# ASM2021.net
KiCad netlist of a schematic drawn in EAGLE
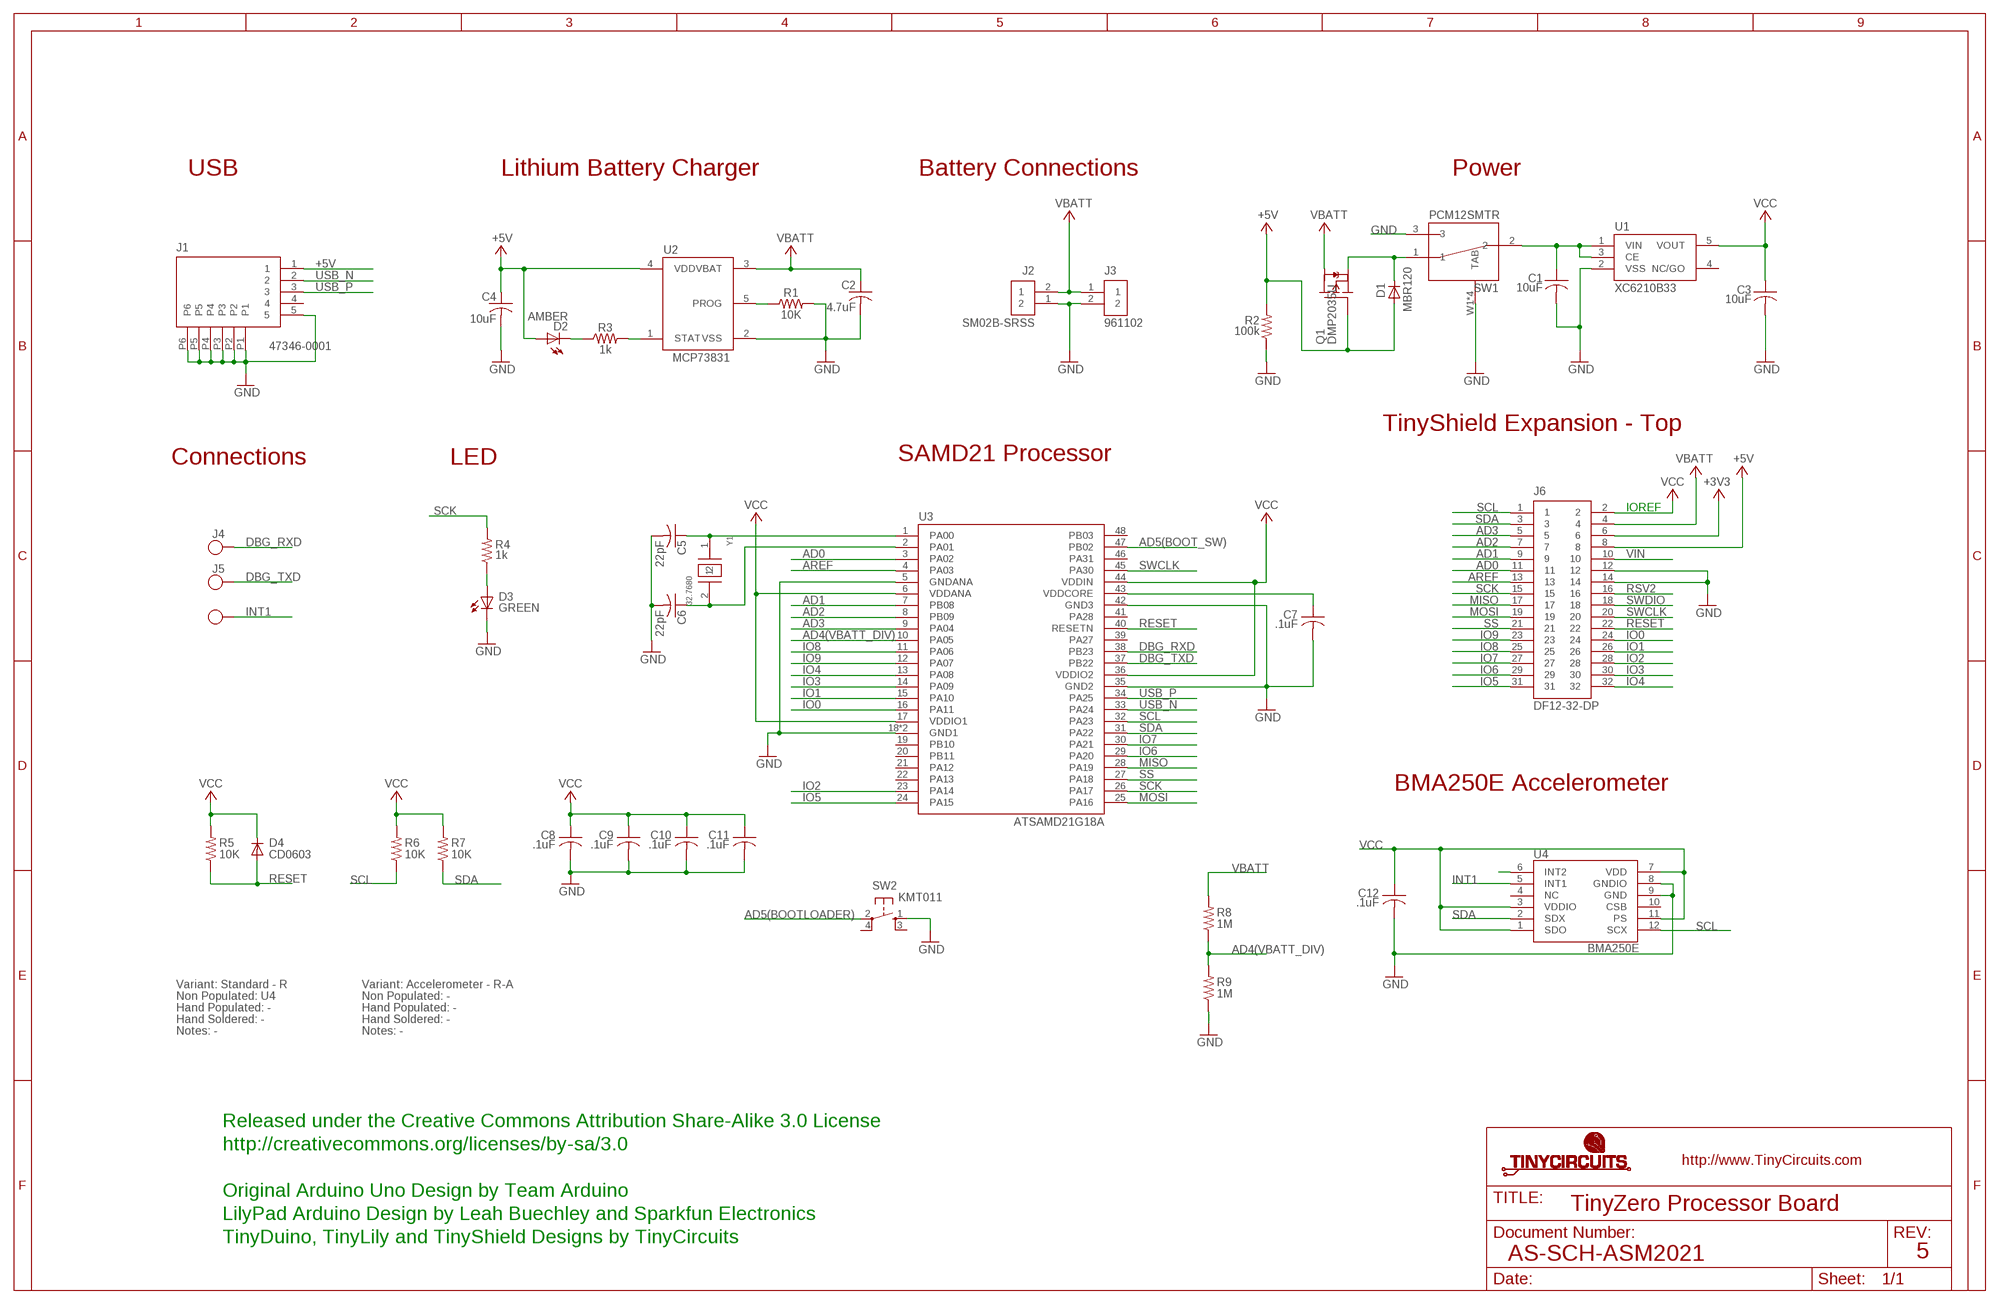
[diagram p0: schematic, sheet 1]

(export (version "E")
  (design (tool "Eeschema 10.0.6"))
  (components
    (comp (ref "C1")
      (value "10uF")
      (footprint "eagle-import:C0603")
      (fields (field (name "PARTNO") "AS-ITM-00002") (field (name "PARTNO_1") "AS-ITM-00002"))
      (libsource (lib "eagle-import") (part "AS-ITM-00002"))
    )
    (comp (ref "C2")
      (value "4.7uF")
      (footprint "eagle-import:C0603")
      (fields (field (name "PARTNO") "AS-ITM-00088") (field (name "PARTNO_1") "AS-ITM-00088"))
      (libsource (lib "eagle-import") (part "AS-ITM-00088"))
    )
    (comp (ref "C3")
      (value "10uF")
      (footprint "eagle-import:C0603")
      (fields (field (name "PARTNO") "AS-ITM-00002") (field (name "PARTNO_1") "AS-ITM-00002"))
      (libsource (lib "eagle-import") (part "AS-ITM-00002"))
    )
    (comp (ref "C4")
      (value "10uF")
      (footprint "eagle-import:C0603")
      (fields (field (name "PARTNO") "AS-ITM-00002") (field (name "PARTNO_1") "AS-ITM-00002"))
      (libsource (lib "eagle-import") (part "AS-ITM-00002"))
    )
    (comp (ref "C5")
      (value "22pF")
      (footprint "eagle-import:C0402")
      (fields (field (name "PARTNO") "AS-ITM-00211") (field (name "PARTNO_1") "AS-ITM-00211"))
      (libsource (lib "eagle-import") (part "AS-ITM-00211"))
    )
    (comp (ref "C6")
      (value "22pF")
      (footprint "eagle-import:C0402")
      (fields (field (name "PARTNO") "AS-ITM-00211") (field (name "PARTNO_1") "AS-ITM-00211"))
      (libsource (lib "eagle-import") (part "AS-ITM-00211"))
    )
    (comp (ref "C7")
      (value ".1uF")
      (footprint "eagle-import:C0402")
      (fields (field (name "PARTNO") "AS-ITM-00008") (field (name "PARTNO_1") "AS-ITM-00008"))
      (libsource (lib "eagle-import") (part "AS-ITM-00008"))
    )
    (comp (ref "C8")
      (value ".1uF")
      (footprint "eagle-import:C0402")
      (fields (field (name "PARTNO") "AS-ITM-00008") (field (name "PARTNO_1") "AS-ITM-00008"))
      (libsource (lib "eagle-import") (part "AS-ITM-00008"))
    )
    (comp (ref "C9")
      (value ".1uF")
      (footprint "eagle-import:C0402")
      (fields (field (name "PARTNO") "AS-ITM-00008") (field (name "PARTNO_1") "AS-ITM-00008"))
      (libsource (lib "eagle-import") (part "AS-ITM-00008"))
    )
    (comp (ref "C10")
      (value ".1uF")
      (footprint "eagle-import:C0402")
      (fields (field (name "PARTNO") "AS-ITM-00008") (field (name "PARTNO_1") "AS-ITM-00008"))
      (libsource (lib "eagle-import") (part "AS-ITM-00008"))
    )
    (comp (ref "C11")
      (value ".1uF")
      (footprint "eagle-import:C0402")
      (fields (field (name "PARTNO") "AS-ITM-00008") (field (name "PARTNO_1") "AS-ITM-00008"))
      (libsource (lib "eagle-import") (part "AS-ITM-00008"))
    )
    (comp (ref "C12")
      (value ".1uF")
      (footprint "eagle-import:C0402")
      (fields (field (name "PARTNO") "AS-ITM-00008") (field (name "PARTNO_1") "AS-ITM-00008"))
      (libsource (lib "eagle-import") (part "AS-ITM-00008"))
    )
    (comp (ref "D1")
      (value "MBR120")
      (footprint "eagle-import:SOD-123FL")
      (fields (field (name "PARTNO") "AS-ITM-00111"))
      (libsource (lib "eagle-import") (part "AS-ITM-00111"))
    )
    (comp (ref "D2")
      (value "AMBER")
      (footprint "eagle-import:LNJ_LED")
      (fields (field (name "PARTNO") "AS-ITM-00026") (field (name "PARTNO_1") "AS-ITM-00026"))
      (libsource (lib "eagle-import") (part "AS-ITM-00026"))
    )
    (comp (ref "D3")
      (value "GREEN")
      (footprint "eagle-import:LNJ_LED")
      (fields (field (name "PARTNO") "AS-ITM-00011") (field (name "PARTNO_1") "AS-ITM-00011"))
      (libsource (lib "eagle-import") (part "AS-ITM-00011"))
    )
    (comp (ref "D4")
      (value "CD0603")
      (footprint "eagle-import:0603")
      (fields (field (name "PARTNO") "AS-ITM-00009") (field (name "PARTNO_1") "AS-ITM-00009"))
      (libsource (lib "eagle-import") (part "AS-ITM-00009"))
    )
    (comp (ref "J1")
      (value "47346-0001")
      (footprint "eagle-import:MICRO_USB")
      (fields (field (name "PARTNO") "AS-ITM-00021"))
      (libsource (lib "eagle-import") (part "AS-ITM-00021"))
    )
    (comp (ref "J2")
      (value "SM02B-SRSS")
      (footprint "eagle-import:JST_SH_2X1")
      (fields (field (name "PARTNO") "AS-ITM-00231"))
      (libsource (lib "eagle-import") (part "AS-ITM-00231"))
    )
    (comp (ref "J3")
      (value "961102")
      (footprint "eagle-import:2X.1_")
      (fields (field (name "PARTNO") "AS-ITM-00044"))
      (libsource (lib "eagle-import") (part "AS-ITM-00044"))
    )
    (comp (ref "J4")
      (value "TEST_POINT")
      (footprint "eagle-import:TEST_POINT_1MM")
      (libsource (lib "eagle-import") (part "TEST_POINT"))
    )
    (comp (ref "J5")
      (value "TEST_POINT")
      (footprint "eagle-import:TEST_POINT_1MM")
      (libsource (lib "eagle-import") (part "TEST_POINT"))
    )
    (comp (ref "J6")
      (value "DF12-32-DP")
      (footprint "eagle-import:DF12-32-DP")
      (fields (field (name "PARTNO") "AS-ITM-00015") (field (name "PARTNO_1") "AS-ITM-00015"))
      (libsource (lib "eagle-import") (part "AS-ITM-00015"))
    )
    (comp (ref "Q1")
      (value "DMP2035U")
      (footprint "eagle-import:SOT23")
      (fields (field (name "PARTNO") "AS-ITM-00024"))
      (libsource (lib "eagle-import") (part "AS-ITM-00024"))
    )
    (comp (ref "R1")
      (value "10K")
      (footprint "eagle-import:0402")
      (fields (field (name "PARTNO") "AS-ITM-00032"))
      (libsource (lib "eagle-import") (part "AS-ITM-00032"))
    )
    (comp (ref "R2")
      (value "100k")
      (footprint "eagle-import:0402")
      (fields (field (name "PARTNO") "AS-ITM-00004") (field (name "PARTNO_1") "AS-ITM-00004"))
      (libsource (lib "eagle-import") (part "AS-ITM-00004"))
    )
    (comp (ref "R3")
      (value "1k")
      (footprint "eagle-import:0402")
      (fields (field (name "PARTNO") "AS-ITM-00003") (field (name "PARTNO_1") "AS-ITM-00003"))
      (libsource (lib "eagle-import") (part "AS-ITM-00003"))
    )
    (comp (ref "R4")
      (value "1k")
      (footprint "eagle-import:0402")
      (fields (field (name "PARTNO") "AS-ITM-00003") (field (name "PARTNO_1") "AS-ITM-00003"))
      (libsource (lib "eagle-import") (part "AS-ITM-00003"))
    )
    (comp (ref "R5")
      (value "10K")
      (footprint "eagle-import:0402")
      (fields (field (name "PARTNO") "AS-ITM-00032") (field (name "PARTNO_1") "AS-ITM-00032"))
      (libsource (lib "eagle-import") (part "AS-ITM-00032"))
    )
    (comp (ref "R6")
      (value "10K")
      (footprint "eagle-import:0402")
      (fields (field (name "PARTNO") "AS-ITM-00032") (field (name "PARTNO_1") "AS-ITM-00032"))
      (libsource (lib "eagle-import") (part "AS-ITM-00032"))
    )
    (comp (ref "R7")
      (value "10K")
      (footprint "eagle-import:0402")
      (fields (field (name "PARTNO") "AS-ITM-00032") (field (name "PARTNO_1") "AS-ITM-00032"))
      (libsource (lib "eagle-import") (part "AS-ITM-00032"))
    )
    (comp (ref "R8")
      (value "1M")
      (footprint "eagle-import:0402")
      (fields (field (name "PARTNO") "AS-ITM-00005") (field (name "PARTNO_1") "AS-ITM-00005"))
      (libsource (lib "eagle-import") (part "AS-ITM-00005"))
    )
    (comp (ref "R9")
      (value "1M")
      (footprint "eagle-import:0402")
      (fields (field (name "PARTNO") "AS-ITM-00005") (field (name "PARTNO_1") "AS-ITM-00005"))
      (libsource (lib "eagle-import") (part "AS-ITM-00005"))
    )
    (comp (ref "SW1")
      (value "PCM12SMTR")
      (footprint "eagle-import:PCM12SMTR")
      (fields (field (name "PARTNO") "AS-ITM-00220"))
      (libsource (lib "eagle-import") (part "AS-ITM-00220"))
    )
    (comp (ref "SW2")
      (value "KMT011")
      (footprint "eagle-import:KMT011")
      (fields (field (name "PARTNO") "AS-ITM-00041"))
      (libsource (lib "eagle-import") (part "AS-ITM-00041"))
    )
    (comp (ref "U1")
      (value "XC6210B33")
      (footprint "eagle-import:SOT-25")
      (fields (field (name "PARTNO") "AS-ITM-00046"))
      (libsource (lib "eagle-import") (part "AS-ITM-00046"))
    )
    (comp (ref "U2")
      (value "MCP73831")
      (footprint "eagle-import:SOT-23")
      (fields (field (name "PARTNO") "AS-ITM-00136"))
      (libsource (lib "eagle-import") (part "AS-ITM-00136"))
    )
    (comp (ref "U3")
      (value "ATSAMD21G18A")
      (footprint "eagle-import:QFN48")
      (fields (field (name "PARTNO") "AS-ITM-00273") (field (name "PARTNO_1") "AS-ITM-00273"))
      (libsource (lib "eagle-import") (part "AS-ITM-00273"))
    )
    (comp (ref "U4")
      (value "BMA250E")
      (footprint "eagle-import:3-AXIS_ACCELEROMETER")
      (fields (field (name "PARTNO") "AS-ITM-00070"))
      (libsource (lib "eagle-import") (part "AS-ITM-00070"))
    )
    (comp (ref "Y1")
      (value "32.7680")
      (footprint "eagle-import:ABS06")
      (fields (field (name "PARTNO") "AS-ITM-00279") (field (name "PARTNO_1") "AS-ITM-00279"))
      (libsource (lib "eagle-import") (part "AS-ITM-00279"))
    )
  )
  (nets
    (net (code "1") (name "+3V3") (class "Default")
      (node (ref "J6") (pin "6") (pinfunction "6_6") (pintype "bidirectional"))
    )
    (net (code "2") (name "+5V") (class "Default")
      (node (ref "C4") (pin "1") (pinfunction "1_1") (pintype "passive"))
      (node (ref "D1") (pin "A") (pinfunction "A_A") (pintype "passive"))
      (node (ref "D2") (pin "A") (pinfunction "A_A") (pintype "passive"))
      (node (ref "J1") (pin "1") (pinfunction "1_1") (pintype "bidirectional"))
      (node (ref "J6") (pin "8") (pinfunction "8_8") (pintype "bidirectional"))
      (node (ref "Q1") (pin "B") (pinfunction "G_B") (pintype "passive"))
      (node (ref "R2") (pin "2") (pinfunction "2_2") (pintype "passive"))
      (node (ref "U2") (pin "4") (pinfunction "VDD_4") (pintype "bidirectional"))
    )
    (net (code "3") (name "/AD0") (class "Default")
      (node (ref "J6") (pin "11") (pinfunction "11_11") (pintype "bidirectional"))
      (node (ref "U3") (pin "3") (pinfunction "PA02_3") (pintype "bidirectional"))
    )
    (net (code "4") (name "/AD1") (class "Default")
      (node (ref "J6") (pin "9") (pinfunction "9_9") (pintype "bidirectional"))
      (node (ref "U3") (pin "7") (pinfunction "PB08_7") (pintype "bidirectional"))
    )
    (net (code "5") (name "/AD2") (class "Default")
      (node (ref "J6") (pin "7") (pinfunction "7_7") (pintype "bidirectional"))
      (node (ref "U3") (pin "8") (pinfunction "PB09_8") (pintype "bidirectional"))
    )
    (net (code "6") (name "/AD3") (class "Default")
      (node (ref "J6") (pin "5") (pinfunction "5_5") (pintype "bidirectional"))
      (node (ref "U3") (pin "9") (pinfunction "PA04_9") (pintype "bidirectional"))
    )
    (net (code "7") (name "/AD4(VBATT_DIV)") (class "Default")
      (node (ref "R8") (pin "1") (pinfunction "1_1") (pintype "passive"))
      (node (ref "R9") (pin "2") (pinfunction "2_2") (pintype "passive"))
      (node (ref "U3") (pin "10") (pinfunction "PA05_10") (pintype "bidirectional"))
    )
    (net (code "8") (name "/AD5(BOOTLOADER)") (class "Default")
      (node (ref "SW2") (pin "2") (pinfunction "2_2") (pintype "passive"))
    )
    (net (code "9") (name "/AD5(BOOT_SW)") (class "Default")
      (node (ref "U3") (pin "47") (pinfunction "PB02_47") (pintype "bidirectional"))
    )
    (net (code "10") (name "/AREF") (class "Default")
      (node (ref "J6") (pin "13") (pinfunction "13_13") (pintype "bidirectional"))
      (node (ref "U3") (pin "4") (pinfunction "PA03_4") (pintype "bidirectional"))
    )
    (net (code "11") (name "/DBG_RXD") (class "Default")
      (node (ref "J4") (pin "P$1") (pinfunction "1_P$1") (pintype "bidirectional"))
      (node (ref "U3") (pin "38") (pinfunction "PB23_38") (pintype "bidirectional"))
    )
    (net (code "12") (name "/DBG_TXD") (class "Default")
      (node (ref "J5") (pin "P$1") (pinfunction "1_P$1") (pintype "bidirectional"))
      (node (ref "U3") (pin "37") (pinfunction "PB22_37") (pintype "bidirectional"))
    )
    (net (code "13") (name "/INT1") (class "Default")
      (node (ref "U4") (pin "5") (pinfunction "INT1_5") (pintype "bidirectional"))
    )
    (net (code "14") (name "/IO0") (class "Default")
      (node (ref "J6") (pin "24") (pinfunction "24_24") (pintype "bidirectional"))
      (node (ref "U3") (pin "16") (pinfunction "PA11_16") (pintype "bidirectional"))
    )
    (net (code "15") (name "/IO1") (class "Default")
      (node (ref "J6") (pin "26") (pinfunction "26_26") (pintype "bidirectional"))
      (node (ref "U3") (pin "15") (pinfunction "PA10_15") (pintype "bidirectional"))
    )
    (net (code "16") (name "/IO2") (class "Default")
      (node (ref "J6") (pin "28") (pinfunction "28_28") (pintype "bidirectional"))
      (node (ref "U3") (pin "23") (pinfunction "PA14_23") (pintype "bidirectional"))
    )
    (net (code "17") (name "/IO3") (class "Default")
      (node (ref "J6") (pin "30") (pinfunction "30_30") (pintype "bidirectional"))
      (node (ref "U3") (pin "14") (pinfunction "PA09_14") (pintype "bidirectional"))
    )
    (net (code "18") (name "/IO4") (class "Default")
      (node (ref "J6") (pin "32") (pinfunction "32_32") (pintype "bidirectional"))
      (node (ref "U3") (pin "13") (pinfunction "PA08_13") (pintype "bidirectional"))
    )
    (net (code "19") (name "/IO5") (class "Default")
      (node (ref "J6") (pin "31") (pinfunction "31_31") (pintype "bidirectional"))
      (node (ref "U3") (pin "24") (pinfunction "PA15_24") (pintype "bidirectional"))
    )
    (net (code "20") (name "/IO6") (class "Default")
      (node (ref "J6") (pin "29") (pinfunction "29_29") (pintype "bidirectional"))
      (node (ref "U3") (pin "29") (pinfunction "PA20_29") (pintype "bidirectional"))
    )
    (net (code "21") (name "/IO7") (class "Default")
      (node (ref "J6") (pin "27") (pinfunction "27_27") (pintype "bidirectional"))
      (node (ref "U3") (pin "30") (pinfunction "PA21_30") (pintype "bidirectional"))
    )
    (net (code "22") (name "/IO8") (class "Default")
      (node (ref "J6") (pin "25") (pinfunction "25_25") (pintype "bidirectional"))
      (node (ref "U3") (pin "11") (pinfunction "PA06_11") (pintype "bidirectional"))
    )
    (net (code "23") (name "/IO9") (class "Default")
      (node (ref "J6") (pin "23") (pinfunction "23_23") (pintype "bidirectional"))
      (node (ref "U3") (pin "12") (pinfunction "PA07_12") (pintype "bidirectional"))
    )
    (net (code "24") (name "/MISO") (class "Default")
      (node (ref "J6") (pin "17") (pinfunction "17_17") (pintype "bidirectional"))
      (node (ref "U3") (pin "28") (pinfunction "PA19_28") (pintype "bidirectional"))
    )
    (net (code "25") (name "/MOSI") (class "Default")
      (node (ref "J6") (pin "19") (pinfunction "19_19") (pintype "bidirectional"))
      (node (ref "U3") (pin "25") (pinfunction "PA16_25") (pintype "bidirectional"))
    )
    (net (code "26") (name "/RESET") (class "Default")
      (node (ref "D4") (pin "A") (pinfunction "A_A") (pintype "passive"))
      (node (ref "J6") (pin "22") (pinfunction "22_22") (pintype "bidirectional"))
      (node (ref "R5") (pin "1") (pinfunction "1_1") (pintype "passive"))
      (node (ref "U3") (pin "40") (pinfunction "RESETN_40") (pintype "bidirectional"))
    )
    (net (code "27") (name "/RSV2") (class "Default")
      (node (ref "J6") (pin "16") (pinfunction "16_16") (pintype "bidirectional"))
    )
    (net (code "28") (name "/SCK") (class "Default")
      (node (ref "J6") (pin "15") (pinfunction "15_15") (pintype "bidirectional"))
      (node (ref "R4") (pin "2") (pinfunction "2_2") (pintype "passive"))
      (node (ref "U3") (pin "26") (pinfunction "PA17_26") (pintype "bidirectional"))
    )
    (net (code "29") (name "/SCL") (class "Default")
      (node (ref "J6") (pin "1") (pinfunction "1_1") (pintype "bidirectional"))
      (node (ref "R6") (pin "1") (pinfunction "1_1") (pintype "passive"))
      (node (ref "U3") (pin "32") (pinfunction "PA23_32") (pintype "bidirectional"))
      (node (ref "U4") (pin "12") (pinfunction "SCX_12") (pintype "bidirectional"))
    )
    (net (code "30") (name "/SDA") (class "Default")
      (node (ref "J6") (pin "3") (pinfunction "3_3") (pintype "bidirectional"))
      (node (ref "R7") (pin "1") (pinfunction "1_1") (pintype "passive"))
      (node (ref "U3") (pin "31") (pinfunction "PA22_31") (pintype "bidirectional"))
      (node (ref "U4") (pin "2") (pinfunction "SDX_2") (pintype "bidirectional"))
    )
    (net (code "31") (name "/SS") (class "Default")
      (node (ref "J6") (pin "21") (pinfunction "21_21") (pintype "bidirectional"))
      (node (ref "U3") (pin "27") (pinfunction "PA18_27") (pintype "bidirectional"))
    )
    (net (code "32") (name "/SWCLK") (class "Default")
      (node (ref "J6") (pin "20") (pinfunction "20_20") (pintype "bidirectional"))
      (node (ref "U3") (pin "45") (pinfunction "PA30_45") (pintype "bidirectional"))
    )
    (net (code "33") (name "/SWDIO") (class "Default")
      (node (ref "J6") (pin "18") (pinfunction "18_18") (pintype "bidirectional"))
    )
    (net (code "34") (name "/USB_N") (class "Default")
      (node (ref "J1") (pin "2") (pinfunction "2_2") (pintype "bidirectional"))
      (node (ref "U3") (pin "33") (pinfunction "PA24_33") (pintype "bidirectional"))
    )
    (net (code "35") (name "/USB_P") (class "Default")
      (node (ref "J1") (pin "3") (pinfunction "3_3") (pintype "bidirectional"))
      (node (ref "U3") (pin "34") (pinfunction "PA25_34") (pintype "bidirectional"))
    )
    (net (code "36") (name "/VIN") (class "Default")
      (node (ref "J6") (pin "10") (pinfunction "10_10") (pintype "bidirectional"))
    )
    (net (code "37") (name "GND") (class "Default")
      (node (ref "C1") (pin "2") (pinfunction "2_2") (pintype "passive"))
      (node (ref "C10") (pin "2") (pinfunction "2_2") (pintype "passive"))
      (node (ref "C11") (pin "2") (pinfunction "2_2") (pintype "passive"))
      (node (ref "C12") (pin "2") (pinfunction "2_2") (pintype "passive"))
      (node (ref "C2") (pin "2") (pinfunction "2_2") (pintype "passive"))
      (node (ref "C3") (pin "2") (pinfunction "2_2") (pintype "passive"))
      (node (ref "C4") (pin "2") (pinfunction "2_2") (pintype "passive"))
      (node (ref "C5") (pin "2") (pinfunction "2_2") (pintype "passive"))
      (node (ref "C6") (pin "2") (pinfunction "2_2") (pintype "passive"))
      (node (ref "C7") (pin "2") (pinfunction "2_2") (pintype "passive"))
      (node (ref "C8") (pin "2") (pinfunction "2_2") (pintype "passive"))
      (node (ref "C9") (pin "2") (pinfunction "2_2") (pintype "passive"))
      (node (ref "D3") (pin "C") (pinfunction "C_C") (pintype "passive"))
      (node (ref "J1") (pin "5") (pinfunction "5_5") (pintype "bidirectional"))
      (node (ref "J1") (pin "P1") (pinfunction "P1_P1") (pintype "bidirectional"))
      (node (ref "J1") (pin "P2") (pinfunction "P2_P2") (pintype "bidirectional"))
      (node (ref "J1") (pin "P3") (pinfunction "P3_P3") (pintype "bidirectional"))
      (node (ref "J1") (pin "P4") (pinfunction "P4_P4") (pintype "bidirectional"))
      (node (ref "J1") (pin "P5") (pinfunction "P5_P5") (pintype "bidirectional"))
      (node (ref "J1") (pin "P6") (pinfunction "P6_P6") (pintype "bidirectional"))
      (node (ref "J2") (pin "1") (pinfunction "2_1") (pintype "bidirectional"))
      (node (ref "J3") (pin "2") (pinfunction "2_2") (pintype "bidirectional"))
      (node (ref "J6") (pin "12") (pinfunction "12_12") (pintype "bidirectional"))
      (node (ref "J6") (pin "14") (pinfunction "14_14") (pintype "bidirectional"))
      (node (ref "R1") (pin "2") (pinfunction "2_2") (pintype "passive"))
      (node (ref "R2") (pin "1") (pinfunction "1_1") (pintype "passive"))
      (node (ref "R9") (pin "1") (pinfunction "1_1") (pintype "passive"))
      (node (ref "SW1") (pin "3") (pinfunction "3_3") (pintype "bidirectional"))
      (node (ref "SW1") (pin "W1") (pinfunction "TAB_W1") (pintype "bidirectional"))
      (node (ref "SW1") (pin "W2") (pinfunction "TAB_W2") (pintype "bidirectional"))
      (node (ref "SW1") (pin "W3") (pinfunction "TAB_W3") (pintype "bidirectional"))
      (node (ref "SW1") (pin "W4") (pinfunction "TAB_W4") (pintype "bidirectional"))
      (node (ref "SW2") (pin "1") (pinfunction "1_1") (pintype "passive"))
      (node (ref "U1") (pin "2") (pinfunction "VSS_2") (pintype "power_in"))
      (node (ref "U2") (pin "2") (pinfunction "VSS_2") (pintype "bidirectional"))
      (node (ref "U3") (pin "18") (pinfunction "GND1_18") (pintype "bidirectional"))
      (node (ref "U3") (pin "35") (pinfunction "GND2_35") (pintype "bidirectional"))
      (node (ref "U3") (pin "42") (pinfunction "GND3_42") (pintype "bidirectional"))
      (node (ref "U3") (pin "5") (pinfunction "GNDANA_5") (pintype "bidirectional"))
      (node (ref "U3") (pin "EXP") (pinfunction "GND1_EXP") (pintype "bidirectional"))
      (node (ref "U4") (pin "8") (pinfunction "GNDIO_8") (pintype "bidirectional"))
      (node (ref "U4") (pin "9") (pinfunction "GND_9") (pintype "bidirectional"))
    )
    (net (code "38") (name "Net-(D2-PadC)") (class "Default")
      (node (ref "D2") (pin "C") (pinfunction "C_C") (pintype "passive"))
      (node (ref "R3") (pin "1") (pinfunction "1_1") (pintype "passive"))
    )
    (net (code "39") (name "Net-(D3-PadA)") (class "Default")
      (node (ref "D3") (pin "A") (pinfunction "A_A") (pintype "passive"))
      (node (ref "R4") (pin "1") (pinfunction "1_1") (pintype "passive"))
    )
    (net (code "40") (name "Net-(Q1-S)") (class "Default")
      (node (ref "D1") (pin "C") (pinfunction "C_C") (pintype "passive"))
      (node (ref "Q1") (pin "E") (pinfunction "S_E") (pintype "passive"))
      (node (ref "SW1") (pin "1") (pinfunction "1_1") (pintype "bidirectional"))
    )
    (net (code "41") (name "Net-(U1-CE)") (class "Default")
      (node (ref "C1") (pin "1") (pinfunction "1_1") (pintype "passive"))
      (node (ref "SW1") (pin "2") (pinfunction "2_2") (pintype "bidirectional"))
      (node (ref "U1") (pin "1") (pinfunction "VIN_1") (pintype "bidirectional"))
      (node (ref "U1") (pin "3") (pinfunction "CE_3") (pintype "bidirectional"))
    )
    (net (code "42") (name "Net-(U2-PROG)") (class "Default")
      (node (ref "R1") (pin "1") (pinfunction "1_1") (pintype "passive"))
      (node (ref "U2") (pin "5") (pinfunction "PROG_5") (pintype "bidirectional"))
    )
    (net (code "43") (name "Net-(U2-STAT)") (class "Default")
      (node (ref "R3") (pin "2") (pinfunction "2_2") (pintype "passive"))
      (node (ref "U2") (pin "1") (pinfunction "STAT_1") (pintype "bidirectional"))
    )
    (net (code "44") (name "Net-(U3-PA00)") (class "Default")
      (node (ref "C5") (pin "1") (pinfunction "1_1") (pintype "passive"))
      (node (ref "U3") (pin "1") (pinfunction "PA00_1") (pintype "bidirectional"))
      (node (ref "Y1") (pin "1") (pinfunction "1_1") (pintype "bidirectional"))
    )
    (net (code "45") (name "Net-(U3-PA01)") (class "Default")
      (node (ref "C6") (pin "1") (pinfunction "1_1") (pintype "passive"))
      (node (ref "U3") (pin "2") (pinfunction "PA01_2") (pintype "bidirectional"))
      (node (ref "Y1") (pin "2") (pinfunction "2_2") (pintype "bidirectional"))
    )
    (net (code "46") (name "Net-(U3-VDDCORE)") (class "Default")
      (node (ref "C7") (pin "1") (pinfunction "1_1") (pintype "passive"))
      (node (ref "U3") (pin "43") (pinfunction "VDDCORE_43") (pintype "bidirectional"))
    )
    (net (code "47") (name "VBATT") (class "Default")
      (node (ref "C2") (pin "1") (pinfunction "1_1") (pintype "passive"))
      (node (ref "J2") (pin "2") (pinfunction "1_2") (pintype "bidirectional"))
      (node (ref "J3") (pin "1") (pinfunction "1_1") (pintype "bidirectional"))
      (node (ref "J6") (pin "4") (pinfunction "4_4") (pintype "bidirectional"))
      (node (ref "Q1") (pin "C") (pinfunction "D_C") (pintype "passive"))
      (node (ref "R8") (pin "2") (pinfunction "2_2") (pintype "passive"))
      (node (ref "U2") (pin "3") (pinfunction "VBAT_3") (pintype "bidirectional"))
    )
    (net (code "48") (name "VCC") (class "Default")
      (node (ref "C10") (pin "1") (pinfunction "1_1") (pintype "passive"))
      (node (ref "C11") (pin "1") (pinfunction "1_1") (pintype "passive"))
      (node (ref "C12") (pin "1") (pinfunction "1_1") (pintype "passive"))
      (node (ref "C3") (pin "1") (pinfunction "1_1") (pintype "passive"))
      (node (ref "C8") (pin "1") (pinfunction "1_1") (pintype "passive"))
      (node (ref "C9") (pin "1") (pinfunction "1_1") (pintype "passive"))
      (node (ref "D4") (pin "C") (pinfunction "C_C") (pintype "passive"))
      (node (ref "J6") (pin "2") (pinfunction "2_2") (pintype "bidirectional"))
      (node (ref "R5") (pin "2") (pinfunction "2_2") (pintype "passive"))
      (node (ref "R6") (pin "2") (pinfunction "2_2") (pintype "passive"))
      (node (ref "R7") (pin "2") (pinfunction "2_2") (pintype "passive"))
      (node (ref "U1") (pin "5") (pinfunction "VOUT_5") (pintype "bidirectional"))
      (node (ref "U3") (pin "17") (pinfunction "VDDIO1_17") (pintype "bidirectional"))
      (node (ref "U3") (pin "36") (pinfunction "VDDIO2_36") (pintype "bidirectional"))
      (node (ref "U3") (pin "44") (pinfunction "VDDIN_44") (pintype "bidirectional"))
      (node (ref "U3") (pin "6") (pinfunction "VDDANA_6") (pintype "bidirectional"))
      (node (ref "U4") (pin "1") (pinfunction "SDO_1") (pintype "bidirectional"))
      (node (ref "U4") (pin "11") (pinfunction "PS_11") (pintype "bidirectional"))
      (node (ref "U4") (pin "3") (pinfunction "VDDIO_3") (pintype "bidirectional"))
      (node (ref "U4") (pin "7") (pinfunction "VDD_7") (pintype "bidirectional"))
    )
    (net (code "49") (name "unconnected-(J1-Pad4)") (class "Default")
      (node (ref "J1") (pin "4") (pinfunction "4_4") (pintype "bidirectional"))
    )
    (net (code "50") (name "unconnected-(SW2-Pad3)") (class "Default")
      (node (ref "SW2") (pin "3") (pinfunction "3_3") (pintype "passive"))
    )
    (net (code "51") (name "unconnected-(SW2-Pad4)") (class "Default")
      (node (ref "SW2") (pin "4") (pinfunction "4_4") (pintype "passive"))
    )
    (net (code "52") (name "unconnected-(U1-NC{slash}GO-Pad4)") (class "Default")
      (node (ref "U1") (pin "4") (pinfunction "NC/GO_4") (pintype "bidirectional"))
    )
    (net (code "53") (name "unconnected-(U3-PA12-Pad21)") (class "Default")
      (node (ref "U3") (pin "21") (pinfunction "PA12_21") (pintype "bidirectional"))
    )
    (net (code "54") (name "unconnected-(U3-PA13-Pad22)") (class "Default")
      (node (ref "U3") (pin "22") (pinfunction "PA13_22") (pintype "bidirectional"))
    )
    (net (code "55") (name "unconnected-(U3-PA27-Pad39)") (class "Default")
      (node (ref "U3") (pin "39") (pinfunction "PA27_39") (pintype "bidirectional"))
    )
    (net (code "56") (name "unconnected-(U3-PA28-Pad41)") (class "Default")
      (node (ref "U3") (pin "41") (pinfunction "PA28_41") (pintype "bidirectional"))
    )
    (net (code "57") (name "unconnected-(U3-PA31-Pad46)") (class "Default")
      (node (ref "U3") (pin "46") (pinfunction "PA31_46") (pintype "bidirectional"))
    )
    (net (code "58") (name "unconnected-(U3-PB03-Pad48)") (class "Default")
      (node (ref "U3") (pin "48") (pinfunction "PB03_48") (pintype "bidirectional"))
    )
    (net (code "59") (name "unconnected-(U3-PB10-Pad19)") (class "Default")
      (node (ref "U3") (pin "19") (pinfunction "PB10_19") (pintype "bidirectional"))
    )
    (net (code "60") (name "unconnected-(U3-PB11-Pad20)") (class "Default")
      (node (ref "U3") (pin "20") (pinfunction "PB11_20") (pintype "bidirectional"))
    )
    (net (code "61") (name "unconnected-(U4-CSB-Pad10)") (class "Default")
      (node (ref "U4") (pin "10") (pinfunction "CSB_10") (pintype "bidirectional"))
    )
    (net (code "62") (name "unconnected-(U4-INT2-Pad6)") (class "Default")
      (node (ref "U4") (pin "6") (pinfunction "INT2_6") (pintype "bidirectional"))
    )
    (net (code "63") (name "unconnected-(U4-NC-Pad4)") (class "Default")
      (node (ref "U4") (pin "4") (pinfunction "NC_4") (pintype "bidirectional"))
    )
  )
)
